# DB23_to_VGA.net
KiCad netlist of a schematic drawn in EAGLE
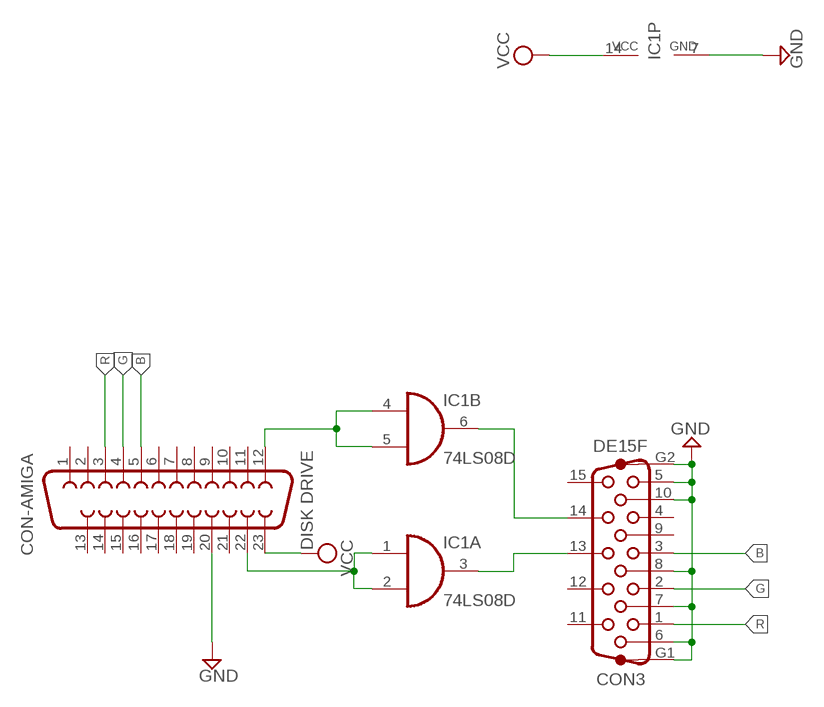
[diagram p0: schematic, sheet 1]

(export (version "E")
  (design (tool "Eeschema 10.0.6"))
  (components
    (comp (ref "CON-AMIGA")
      (value "DISK DRIVE")
      (footprint "eagle-import:DB23")
      (libsource (lib "eagle-import") (part "DB23"))
    )
    (comp (ref "CON3")
      (value "DE15F")
      (footprint "eagle-import:VGA-FHP")
      (libsource (lib "eagle-import") (part "VGA-FHP"))
    )
    (comp (ref "IC1")
      (value "74LS08D")
      (footprint "eagle-import:SO14")
      (libsource (lib "eagle-import") (part "7408DLS"))
    )
  )
  (nets
    (net (code "1") (name "B") (class "Default")
      (node (ref "CON-AMIGA") (pin "5") (pinfunction "5_5") (pintype "passive"))
      (node (ref "CON3") (pin "3") (pinfunction "3_3") (pintype "passive"))
    )
    (net (code "2") (name "G") (class "Default")
      (node (ref "CON-AMIGA") (pin "4") (pinfunction "4_4") (pintype "passive"))
      (node (ref "CON3") (pin "2") (pinfunction "2_2") (pintype "passive"))
    )
    (net (code "3") (name "GND") (class "Default")
      (node (ref "CON-AMIGA") (pin "20") (pinfunction "20_20") (pintype "passive"))
      (node (ref "CON3") (pin "10") (pinfunction "10_10") (pintype "passive"))
      (node (ref "CON3") (pin "5") (pinfunction "5_5") (pintype "passive"))
      (node (ref "CON3") (pin "6") (pinfunction "6_6") (pintype "passive"))
      (node (ref "CON3") (pin "7") (pinfunction "7_7") (pintype "passive"))
      (node (ref "CON3") (pin "8") (pinfunction "8_8") (pintype "passive"))
      (node (ref "CON3") (pin "G1") (pinfunction "G1_G1") (pintype "passive"))
      (node (ref "CON3") (pin "G2") (pinfunction "G2_G2") (pintype "passive"))
      (node (ref "IC1") (pin "7") (pinfunction "GND_7") (pintype "power_in"))
    )
    (net (code "4") (name "Net-(IC1A-I0)") (class "Default")
      (node (ref "CON-AMIGA") (pin "22") (pinfunction "22_22") (pintype "passive"))
      (node (ref "IC1") (pin "1") (pinfunction "I0_1") (pintype "input"))
      (node (ref "IC1") (pin "2") (pinfunction "I1_2") (pintype "input"))
    )
    (net (code "5") (name "Net-(IC1A-O)") (class "Default")
      (node (ref "CON3") (pin "13") (pinfunction "13_13") (pintype "passive"))
      (node (ref "IC1") (pin "3") (pinfunction "O_3") (pintype "output"))
    )
    (net (code "6") (name "Net-(IC1B-I0)") (class "Default")
      (node (ref "CON-AMIGA") (pin "12") (pinfunction "12_12") (pintype "passive"))
      (node (ref "IC1") (pin "4") (pinfunction "I0_4") (pintype "input"))
      (node (ref "IC1") (pin "5") (pinfunction "I1_5") (pintype "input"))
    )
    (net (code "7") (name "Net-(IC1B-O)") (class "Default")
      (node (ref "CON3") (pin "14") (pinfunction "14_14") (pintype "passive"))
      (node (ref "IC1") (pin "6") (pinfunction "O_6") (pintype "output"))
    )
    (net (code "8") (name "R") (class "Default")
      (node (ref "CON-AMIGA") (pin "3") (pinfunction "3_3") (pintype "passive"))
      (node (ref "CON3") (pin "1") (pinfunction "1_1") (pintype "passive"))
    )
    (net (code "9") (name "VCC") (class "Default")
      (node (ref "CON-AMIGA") (pin "23") (pinfunction "23_23") (pintype "passive"))
      (node (ref "IC1") (pin "14") (pinfunction "VCC_14") (pintype "power_in"))
    )
    (net (code "10") (name "unconnected-(CON-AMIGA-Pad1)") (class "Default")
      (node (ref "CON-AMIGA") (pin "1") (pinfunction "1_1") (pintype "passive"))
    )
    (net (code "11") (name "unconnected-(CON-AMIGA-Pad2)") (class "Default")
      (node (ref "CON-AMIGA") (pin "2") (pinfunction "2_2") (pintype "passive"))
    )
    (net (code "12") (name "unconnected-(CON-AMIGA-Pad6)") (class "Default")
      (node (ref "CON-AMIGA") (pin "6") (pinfunction "6_6") (pintype "passive"))
    )
    (net (code "13") (name "unconnected-(CON-AMIGA-Pad7)") (class "Default")
      (node (ref "CON-AMIGA") (pin "7") (pinfunction "7_7") (pintype "passive"))
    )
    (net (code "14") (name "unconnected-(CON-AMIGA-Pad8)") (class "Default")
      (node (ref "CON-AMIGA") (pin "8") (pinfunction "8_8") (pintype "passive"))
    )
    (net (code "15") (name "unconnected-(CON-AMIGA-Pad9)") (class "Default")
      (node (ref "CON-AMIGA") (pin "9") (pinfunction "9_9") (pintype "passive"))
    )
    (net (code "16") (name "unconnected-(CON-AMIGA-Pad10)") (class "Default")
      (node (ref "CON-AMIGA") (pin "10") (pinfunction "10_10") (pintype "passive"))
    )
    (net (code "17") (name "unconnected-(CON-AMIGA-Pad11)") (class "Default")
      (node (ref "CON-AMIGA") (pin "11") (pinfunction "11_11") (pintype "passive"))
    )
    (net (code "18") (name "unconnected-(CON-AMIGA-Pad13)") (class "Default")
      (node (ref "CON-AMIGA") (pin "13") (pinfunction "13_13") (pintype "passive"))
    )
    (net (code "19") (name "unconnected-(CON-AMIGA-Pad14)") (class "Default")
      (node (ref "CON-AMIGA") (pin "14") (pinfunction "14_14") (pintype "passive"))
    )
    (net (code "20") (name "unconnected-(CON-AMIGA-Pad15)") (class "Default")
      (node (ref "CON-AMIGA") (pin "15") (pinfunction "15_15") (pintype "passive"))
    )
    (net (code "21") (name "unconnected-(CON-AMIGA-Pad16)") (class "Default")
      (node (ref "CON-AMIGA") (pin "16") (pinfunction "16_16") (pintype "passive"))
    )
    (net (code "22") (name "unconnected-(CON-AMIGA-Pad17)") (class "Default")
      (node (ref "CON-AMIGA") (pin "17") (pinfunction "17_17") (pintype "passive"))
    )
    (net (code "23") (name "unconnected-(CON-AMIGA-Pad18)") (class "Default")
      (node (ref "CON-AMIGA") (pin "18") (pinfunction "18_18") (pintype "passive"))
    )
    (net (code "24") (name "unconnected-(CON-AMIGA-Pad19)") (class "Default")
      (node (ref "CON-AMIGA") (pin "19") (pinfunction "19_19") (pintype "passive"))
    )
    (net (code "25") (name "unconnected-(CON-AMIGA-Pad21)") (class "Default")
      (node (ref "CON-AMIGA") (pin "21") (pinfunction "21_21") (pintype "passive"))
    )
    (net (code "26") (name "unconnected-(CON3-Pad4)") (class "Default")
      (node (ref "CON3") (pin "4") (pinfunction "4_4") (pintype "passive"))
    )
    (net (code "27") (name "unconnected-(CON3-Pad9)") (class "Default")
      (node (ref "CON3") (pin "9") (pinfunction "9_9") (pintype "passive"))
    )
    (net (code "28") (name "unconnected-(CON3-Pad11)") (class "Default")
      (node (ref "CON3") (pin "11") (pinfunction "11_11") (pintype "passive"))
    )
    (net (code "29") (name "unconnected-(CON3-Pad12)") (class "Default")
      (node (ref "CON3") (pin "12") (pinfunction "12_12") (pintype "passive"))
    )
    (net (code "30") (name "unconnected-(CON3-Pad15)") (class "Default")
      (node (ref "CON3") (pin "15") (pinfunction "15_15") (pintype "passive"))
    )
  )
)
